# 32nbIoTrpi.net
KiCad netlist of a schematic drawn in EAGLE
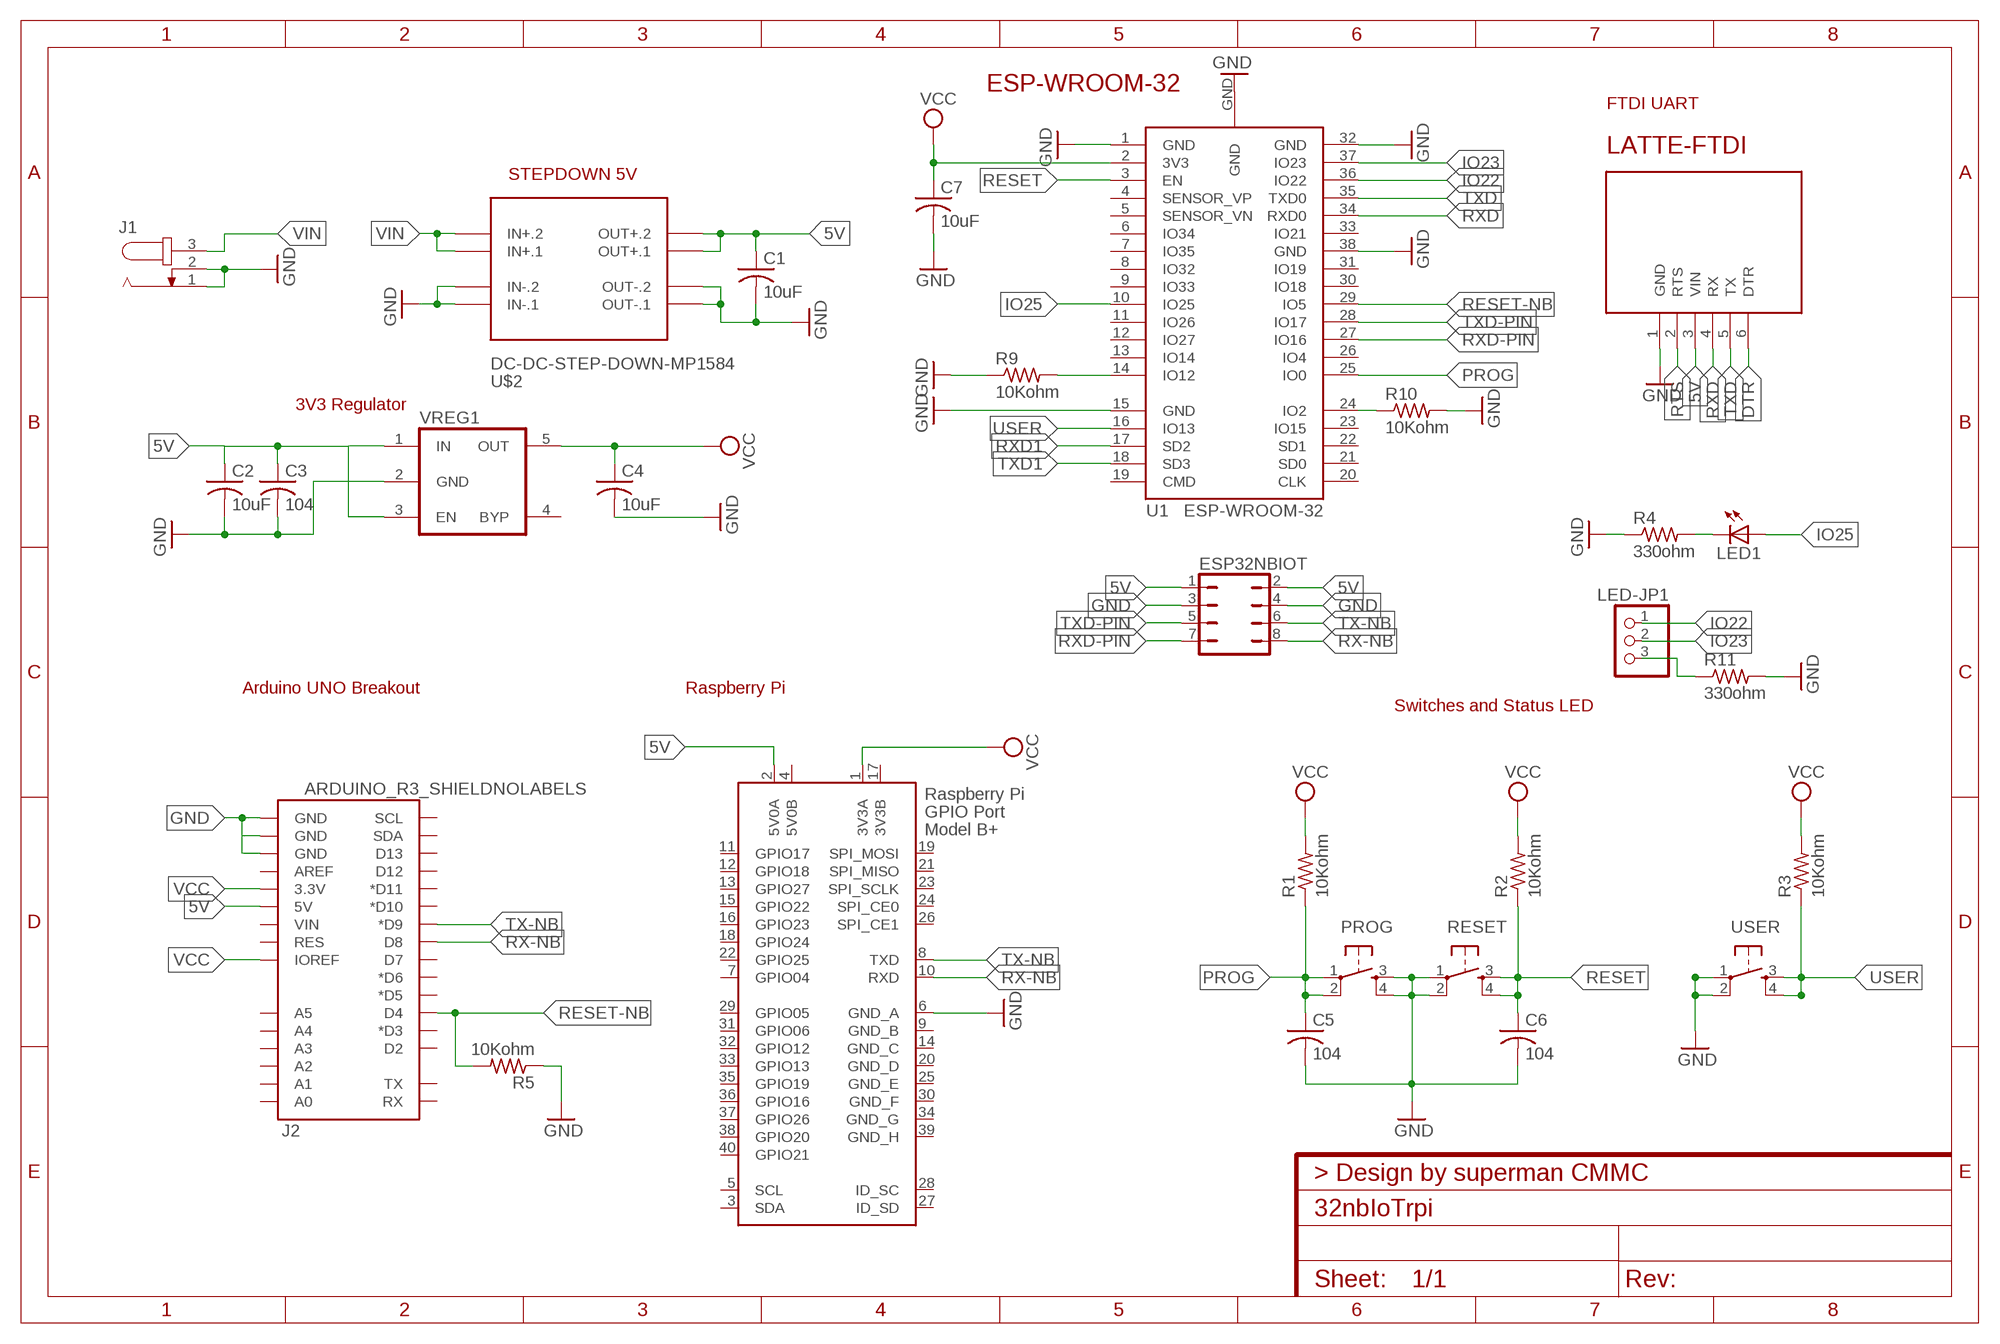
[diagram p0: schematic, sheet 1]

(export (version "E")
  (design (tool "Eeschema 10.0.6"))
  (components
    (comp (ref "C1")
      (value "10uF")
      (footprint "eagle-import:C0805")
      (libsource (lib "eagle-import") (part "C-USC0805"))
    )
    (comp (ref "C2")
      (value "10uF")
      (footprint "eagle-import:C0805")
      (libsource (lib "eagle-import") (part "C-USC0805"))
    )
    (comp (ref "C3")
      (value "104")
      (footprint "eagle-import:C0805")
      (libsource (lib "eagle-import") (part "C-USC0805"))
    )
    (comp (ref "C4")
      (value "10uF")
      (footprint "eagle-import:C0805")
      (libsource (lib "eagle-import") (part "C-USC0805"))
    )
    (comp (ref "C5")
      (value "104")
      (footprint "eagle-import:C0805")
      (libsource (lib "eagle-import") (part "C-USC0805"))
    )
    (comp (ref "C6")
      (value "104")
      (footprint "eagle-import:C0805")
      (libsource (lib "eagle-import") (part "C-USC0805"))
    )
    (comp (ref "C7")
      (value "10uF")
      (footprint "eagle-import:C0805")
      (libsource (lib "eagle-import") (part "C-USC0805"))
    )
    (comp (ref "ESP32NBIOT")
      (value "JP4Q")
      (footprint "eagle-import:JP4Q")
      (libsource (lib "eagle-import") (part "JP4Q"))
    )
    (comp (ref "J1")
      (value "JACK-PLUG1")
      (footprint "eagle-import:SPC4078")
      (libsource (lib "eagle-import") (part "JACK-PLUG1"))
    )
    (comp (ref "J2")
      (value "ARDUINO_R3_SHIELDNOLABELS")
      (footprint "eagle-import:UNO_R3_SHIELD_NOLABELS")
      (libsource (lib "eagle-import") (part "ARDUINO_R3_SHIELDNOLABELS"))
    )
    (comp (ref "LATTE-FTDI")
      (value "FTDI")
      (footprint "eagle-import:CMMC-FTDI")
      (libsource (lib "eagle-import") (part "FTDI"))
    )
    (comp (ref "LED-JP1")
      (value "PINHD-1X3/90")
      (footprint "eagle-import:1X03_90")
      (libsource (lib "eagle-import") (part "PINHD-1X3/90"))
    )
    (comp (ref "LED1")
      (value "LEDCHIPLED_0805")
      (footprint "eagle-import:CHIPLED_0805")
      (libsource (lib "eagle-import") (part "LEDCHIPLED_0805"))
    )
    (comp (ref "PROG")
      (value "TAC_SWITCHPTH")
      (footprint "eagle-import:TACTILE-PTH")
      (libsource (lib "eagle-import") (part "TAC_SWITCHPTH"))
    )
    (comp (ref "R1")
      (value "10Kohm")
      (footprint "eagle-import:R0805W")
      (libsource (lib "eagle-import") (part "R-US_R0805W"))
    )
    (comp (ref "R2")
      (value "10Kohm")
      (footprint "eagle-import:R0805W")
      (libsource (lib "eagle-import") (part "R-US_R0805W"))
    )
    (comp (ref "R3")
      (value "10Kohm")
      (footprint "eagle-import:R0805W")
      (libsource (lib "eagle-import") (part "R-US_R0805W"))
    )
    (comp (ref "R4")
      (value "330ohm")
      (footprint "eagle-import:R0805W")
      (libsource (lib "eagle-import") (part "R-US_R0805W"))
    )
    (comp (ref "R5")
      (value "10Kohm")
      (footprint "eagle-import:R0805W")
      (libsource (lib "eagle-import") (part "R-US_R0805W"))
    )
    (comp (ref "R9")
      (value "10Kohm")
      (footprint "eagle-import:R0805W")
      (libsource (lib "eagle-import") (part "R-US_R0805W"))
    )
    (comp (ref "R10")
      (value "10Kohm")
      (footprint "eagle-import:R0805W")
      (libsource (lib "eagle-import") (part "R-US_R0805W"))
    )
    (comp (ref "R11")
      (value "330ohm")
      (footprint "eagle-import:R0805W")
      (libsource (lib "eagle-import") (part "R-US_R0805W"))
    )
    (comp (ref "RESET")
      (value "TAC_SWITCHPTH")
      (footprint "eagle-import:TACTILE-PTH")
      (libsource (lib "eagle-import") (part "TAC_SWITCHPTH"))
    )
    (comp (ref "U$2")
      (value "DC-DC-STEP-DOWN-MP1584")
      (footprint "eagle-import:DC-DC-STEP-DOWN-MP1584")
      (libsource (lib "eagle-import") (part "DC-DC-STEP-DOWN-MP1584"))
    )
    (comp (ref "U1")
      (value "ESP-WROOM-32")
      (footprint "eagle-import:ESP-WROOM-32")
      (libsource (lib "eagle-import") (part "ESP-WROOM-32"))
    )
    (comp (ref "USER")
      (value "TAC_SWITCHPTH")
      (footprint "eagle-import:TACTILE-PTH")
      (libsource (lib "eagle-import") (part "TAC_SWITCHPTH"))
    )
    (comp (ref "VREG1")
      (value "VREG_5PINS-SOT-23-5")
      (footprint "eagle-import:SOT-23-5")
      (libsource (lib "eagle-import") (part "VREG_5PINS-SOT-23-5"))
    )
    (comp (ref "X2")
      (value "RASPI_BOARD_B+#_E0")
      (footprint "eagle-import:RASPI_BOARD_B+_EDGES_0DRILL")
      (libsource (lib "eagle-import") (part "RASPI_BOARD_B+#_E0"))
    )
  )
  (nets
    (net (code "1") (name "/3V3B") (class "Default")
      (node (ref "X2") (pin "17") (pinfunction "3V3B_17") (pintype "power_in"))
    )
    (net (code "2") (name "/5V0B") (class "Default")
      (node (ref "X2") (pin "4") (pinfunction "5V0B_4") (pintype "power_in"))
    )
    (net (code "3") (name "/GND_B") (class "Default")
      (node (ref "X2") (pin "9") (pinfunction "GND_B_9") (pintype "power_in"))
    )
    (net (code "4") (name "/GND_C") (class "Default")
      (node (ref "X2") (pin "14") (pinfunction "GND_C_14") (pintype "power_in"))
    )
    (net (code "5") (name "/GND_D") (class "Default")
      (node (ref "X2") (pin "20") (pinfunction "GND_D_20") (pintype "power_in"))
    )
    (net (code "6") (name "/GND_E") (class "Default")
      (node (ref "X2") (pin "25") (pinfunction "GND_E_25") (pintype "power_in"))
    )
    (net (code "7") (name "/GND_F") (class "Default")
      (node (ref "X2") (pin "30") (pinfunction "GND_F_30") (pintype "power_in"))
    )
    (net (code "8") (name "/GND_G") (class "Default")
      (node (ref "X2") (pin "34") (pinfunction "GND_G_34") (pintype "power_in"))
    )
    (net (code "9") (name "/GND_H") (class "Default")
      (node (ref "X2") (pin "39") (pinfunction "GND_H_39") (pintype "power_in"))
    )
    (net (code "10") (name "5V") (class "Default")
      (node (ref "C1") (pin "1") (pinfunction "1_1") (pintype "passive"))
      (node (ref "C2") (pin "1") (pinfunction "1_1") (pintype "passive"))
      (node (ref "C3") (pin "1") (pinfunction "1_1") (pintype "passive"))
      (node (ref "ESP32NBIOT") (pin "1") (pinfunction "1_1") (pintype "passive"))
      (node (ref "ESP32NBIOT") (pin "2") (pinfunction "2_2") (pintype "passive"))
      (node (ref "J2") (pin "5V") (pinfunction "5V_5V") (pintype "bidirectional"))
      (node (ref "LATTE-FTDI") (pin "3") (pinfunction "VIN_3") (pintype "bidirectional"))
      (node (ref "U$2") (pin "OUT+.1") (pinfunction "OUT+.1_OUT+.1") (pintype "bidirectional"))
      (node (ref "U$2") (pin "OUT+.2") (pinfunction "OUT+.2_OUT+.2") (pintype "bidirectional"))
      (node (ref "VREG1") (pin "1") (pinfunction "IN_1") (pintype "bidirectional"))
      (node (ref "VREG1") (pin "3") (pinfunction "EN_3") (pintype "bidirectional"))
      (node (ref "X2") (pin "2") (pinfunction "5V0A_2") (pintype "power_in"))
    )
    (net (code "11") (name "DTR") (class "Default")
      (node (ref "LATTE-FTDI") (pin "6") (pinfunction "DTR_6") (pintype "bidirectional"))
    )
    (net (code "12") (name "GND") (class "Default")
      (node (ref "C1") (pin "2") (pinfunction "2_2") (pintype "passive"))
      (node (ref "C2") (pin "2") (pinfunction "2_2") (pintype "passive"))
      (node (ref "C3") (pin "2") (pinfunction "2_2") (pintype "passive"))
      (node (ref "C4") (pin "2") (pinfunction "2_2") (pintype "passive"))
      (node (ref "C5") (pin "2") (pinfunction "2_2") (pintype "passive"))
      (node (ref "C6") (pin "2") (pinfunction "2_2") (pintype "passive"))
      (node (ref "C7") (pin "2") (pinfunction "2_2") (pintype "passive"))
      (node (ref "ESP32NBIOT") (pin "3") (pinfunction "3_3") (pintype "passive"))
      (node (ref "ESP32NBIOT") (pin "4") (pinfunction "4_4") (pintype "passive"))
      (node (ref "J1") (pin "1") (pinfunction "1_1") (pintype "passive"))
      (node (ref "J1") (pin "2") (pinfunction "2_2") (pintype "passive"))
      (node (ref "J2") (pin "GND@0") (pinfunction "GND_GND@0") (pintype "bidirectional"))
      (node (ref "J2") (pin "GND@1") (pinfunction "GND_GND@1") (pintype "bidirectional"))
      (node (ref "J2") (pin "GND@2") (pinfunction "GND_GND@2") (pintype "bidirectional"))
      (node (ref "LATTE-FTDI") (pin "1") (pinfunction "GND_1") (pintype "bidirectional"))
      (node (ref "PROG") (pin "3") (pinfunction "3_3") (pintype "passive"))
      (node (ref "PROG") (pin "4") (pinfunction "4_4") (pintype "passive"))
      (node (ref "R10") (pin "2") (pinfunction "2_2") (pintype "passive"))
      (node (ref "R11") (pin "2") (pinfunction "2_2") (pintype "passive"))
      (node (ref "R4") (pin "1") (pinfunction "1_1") (pintype "passive"))
      (node (ref "R5") (pin "1") (pinfunction "1_1") (pintype "passive"))
      (node (ref "R9") (pin "1") (pinfunction "1_1") (pintype "passive"))
      (node (ref "RESET") (pin "1") (pinfunction "1_1") (pintype "passive"))
      (node (ref "RESET") (pin "2") (pinfunction "2_2") (pintype "passive"))
      (node (ref "U$2") (pin "IN-.1") (pinfunction "IN-.1_IN-.1") (pintype "bidirectional"))
      (node (ref "U$2") (pin "IN-.2") (pinfunction "IN-.2_IN-.2") (pintype "bidirectional"))
      (node (ref "U$2") (pin "OUT-.1") (pinfunction "OUT-.1_OUT-.1") (pintype "bidirectional"))
      (node (ref "U$2") (pin "OUT-.2") (pinfunction "OUT-.2_OUT-.2") (pintype "bidirectional"))
      (node (ref "U1") (pin "1") (pinfunction "GND_1") (pintype "power_in"))
      (node (ref "U1") (pin "15") (pinfunction "GND_15") (pintype "power_in"))
      (node (ref "U1") (pin "32") (pinfunction "GND_32") (pintype "power_in"))
      (node (ref "U1") (pin "38") (pinfunction "GND_38") (pintype "power_in"))
      (node (ref "U1") (pin "GND") (pinfunction "GND_GND") (pintype "bidirectional"))
      (node (ref "USER") (pin "1") (pinfunction "1_1") (pintype "passive"))
      (node (ref "USER") (pin "2") (pinfunction "2_2") (pintype "passive"))
      (node (ref "VREG1") (pin "2") (pinfunction "GND_2") (pintype "bidirectional"))
      (node (ref "X2") (pin "6") (pinfunction "GND_A_6") (pintype "power_in"))
    )
    (net (code "13") (name "IO22") (class "Default")
      (node (ref "LED-JP1") (pin "1") (pinfunction "1_1") (pintype "passive"))
      (node (ref "U1") (pin "36") (pinfunction "IO22_36") (pintype "bidirectional"))
    )
    (net (code "14") (name "IO23") (class "Default")
      (node (ref "LED-JP1") (pin "2") (pinfunction "2_2") (pintype "passive"))
      (node (ref "U1") (pin "37") (pinfunction "IO23_37") (pintype "bidirectional"))
    )
    (net (code "15") (name "IO25") (class "Default")
      (node (ref "LED1") (pin "A") (pinfunction "A_A") (pintype "passive"))
      (node (ref "U1") (pin "10") (pinfunction "IO25_10") (pintype "bidirectional"))
    )
    (net (code "16") (name "Net-(LED-JP1-Pad3)") (class "Default")
      (node (ref "LED-JP1") (pin "3") (pinfunction "3_3") (pintype "passive"))
      (node (ref "R11") (pin "1") (pinfunction "1_1") (pintype "passive"))
    )
    (net (code "17") (name "Net-(LED1-PadC)") (class "Default")
      (node (ref "LED1") (pin "C") (pinfunction "C_C") (pintype "passive"))
      (node (ref "R4") (pin "2") (pinfunction "2_2") (pintype "passive"))
    )
    (net (code "18") (name "Net-(U1-IO2)") (class "Default")
      (node (ref "R10") (pin "1") (pinfunction "1_1") (pintype "passive"))
      (node (ref "U1") (pin "24") (pinfunction "IO2_24") (pintype "bidirectional"))
    )
    (net (code "19") (name "Net-(U1-IO12)") (class "Default")
      (node (ref "R9") (pin "2") (pinfunction "2_2") (pintype "passive"))
      (node (ref "U1") (pin "14") (pinfunction "IO12_14") (pintype "bidirectional"))
    )
    (net (code "20") (name "PROG") (class "Default")
      (node (ref "C5") (pin "1") (pinfunction "1_1") (pintype "passive"))
      (node (ref "PROG") (pin "1") (pinfunction "1_1") (pintype "passive"))
      (node (ref "PROG") (pin "2") (pinfunction "2_2") (pintype "passive"))
      (node (ref "R1") (pin "1") (pinfunction "1_1") (pintype "passive"))
      (node (ref "U1") (pin "25") (pinfunction "IO0_25") (pintype "bidirectional"))
    )
    (net (code "21") (name "RESET") (class "Default")
      (node (ref "C6") (pin "1") (pinfunction "1_1") (pintype "passive"))
      (node (ref "R2") (pin "1") (pinfunction "1_1") (pintype "passive"))
      (node (ref "RESET") (pin "3") (pinfunction "3_3") (pintype "passive"))
      (node (ref "RESET") (pin "4") (pinfunction "4_4") (pintype "passive"))
      (node (ref "U1") (pin "3") (pinfunction "EN_3") (pintype "input"))
    )
    (net (code "22") (name "RESET-NB") (class "Default")
      (node (ref "J2") (pin "D4") (pinfunction "D4_D4") (pintype "bidirectional"))
      (node (ref "R5") (pin "2") (pinfunction "2_2") (pintype "passive"))
      (node (ref "U1") (pin "29") (pinfunction "IO5_29") (pintype "bidirectional"))
    )
    (net (code "23") (name "RTS") (class "Default")
      (node (ref "LATTE-FTDI") (pin "2") (pinfunction "RTS_2") (pintype "bidirectional"))
    )
    (net (code "24") (name "RX-NB") (class "Default")
      (node (ref "ESP32NBIOT") (pin "8") (pinfunction "8_8") (pintype "passive"))
      (node (ref "J2") (pin "D8") (pinfunction "D8_D8") (pintype "bidirectional"))
      (node (ref "X2") (pin "10") (pinfunction "RXD_10") (pintype "bidirectional"))
    )
    (net (code "25") (name "RXD") (class "Default")
      (node (ref "LATTE-FTDI") (pin "4") (pinfunction "RX_4") (pintype "bidirectional"))
      (node (ref "U1") (pin "34") (pinfunction "RXD0_34") (pintype "bidirectional"))
    )
    (net (code "26") (name "RXD-PIN") (class "Default")
      (node (ref "ESP32NBIOT") (pin "7") (pinfunction "7_7") (pintype "passive"))
      (node (ref "U1") (pin "27") (pinfunction "IO16_27") (pintype "bidirectional"))
    )
    (net (code "27") (name "RXD1") (class "Default")
      (node (ref "U1") (pin "17") (pinfunction "SD2_17") (pintype "bidirectional"))
    )
    (net (code "28") (name "TX-NB") (class "Default")
      (node (ref "ESP32NBIOT") (pin "6") (pinfunction "6_6") (pintype "passive"))
      (node (ref "J2") (pin "D9") (pinfunction "*D9_D9") (pintype "bidirectional"))
      (node (ref "X2") (pin "8") (pinfunction "TXD_8") (pintype "bidirectional"))
    )
    (net (code "29") (name "TXD") (class "Default")
      (node (ref "LATTE-FTDI") (pin "5") (pinfunction "TX_5") (pintype "bidirectional"))
      (node (ref "U1") (pin "35") (pinfunction "TXD0_35") (pintype "bidirectional"))
    )
    (net (code "30") (name "TXD-PIN") (class "Default")
      (node (ref "ESP32NBIOT") (pin "5") (pinfunction "5_5") (pintype "passive"))
      (node (ref "U1") (pin "28") (pinfunction "IO17_28") (pintype "bidirectional"))
    )
    (net (code "31") (name "TXD1") (class "Default")
      (node (ref "U1") (pin "18") (pinfunction "SD3_18") (pintype "bidirectional"))
    )
    (net (code "32") (name "USER") (class "Default")
      (node (ref "R3") (pin "1") (pinfunction "1_1") (pintype "passive"))
      (node (ref "U1") (pin "16") (pinfunction "IO13_16") (pintype "bidirectional"))
      (node (ref "USER") (pin "3") (pinfunction "3_3") (pintype "passive"))
      (node (ref "USER") (pin "4") (pinfunction "4_4") (pintype "passive"))
    )
    (net (code "33") (name "VCC") (class "Default")
      (node (ref "C4") (pin "1") (pinfunction "1_1") (pintype "passive"))
      (node (ref "C7") (pin "1") (pinfunction "1_1") (pintype "passive"))
      (node (ref "J2") (pin "3.3V") (pinfunction "3.3V_3.3V") (pintype "bidirectional"))
      (node (ref "J2") (pin "IOREF") (pinfunction "IOREF_IOREF") (pintype "bidirectional"))
      (node (ref "R1") (pin "2") (pinfunction "2_2") (pintype "passive"))
      (node (ref "R2") (pin "2") (pinfunction "2_2") (pintype "passive"))
      (node (ref "R3") (pin "2") (pinfunction "2_2") (pintype "passive"))
      (node (ref "U1") (pin "2") (pinfunction "3V3_2") (pintype "power_in"))
      (node (ref "VREG1") (pin "5") (pinfunction "OUT_5") (pintype "bidirectional"))
      (node (ref "X2") (pin "1") (pinfunction "3V3A_1") (pintype "power_in"))
    )
    (net (code "34") (name "VIN") (class "Default")
      (node (ref "J1") (pin "3") (pinfunction "3_3") (pintype "passive"))
      (node (ref "U$2") (pin "IN+.1") (pinfunction "IN+.1_IN+.1") (pintype "bidirectional"))
      (node (ref "U$2") (pin "IN+.2") (pinfunction "IN+.2_IN+.2") (pintype "bidirectional"))
    )
    (net (code "35") (name "unconnected-(J2-*D3-PadD3)") (class "Default")
      (node (ref "J2") (pin "D3") (pinfunction "*D3_D3") (pintype "bidirectional"))
    )
    (net (code "36") (name "unconnected-(J2-*D5-PadD5)") (class "Default")
      (node (ref "J2") (pin "D5") (pinfunction "*D5_D5") (pintype "bidirectional"))
    )
    (net (code "37") (name "unconnected-(J2-*D6-PadD6)") (class "Default")
      (node (ref "J2") (pin "D6") (pinfunction "*D6_D6") (pintype "bidirectional"))
    )
    (net (code "38") (name "unconnected-(J2-*D10-PadD10)") (class "Default")
      (node (ref "J2") (pin "D10") (pinfunction "*D10_D10") (pintype "bidirectional"))
    )
    (net (code "39") (name "unconnected-(J2-*D11-PadD11)") (class "Default")
      (node (ref "J2") (pin "D11") (pinfunction "*D11_D11") (pintype "bidirectional"))
    )
    (net (code "40") (name "unconnected-(J2-PadA0)") (class "Default")
      (node (ref "J2") (pin "A0") (pinfunction "A0_A0") (pintype "bidirectional"))
    )
    (net (code "41") (name "unconnected-(J2-PadA1)") (class "Default")
      (node (ref "J2") (pin "A1") (pinfunction "A1_A1") (pintype "bidirectional"))
    )
    (net (code "42") (name "unconnected-(J2-PadA2)") (class "Default")
      (node (ref "J2") (pin "A2") (pinfunction "A2_A2") (pintype "bidirectional"))
    )
    (net (code "43") (name "unconnected-(J2-PadA3)") (class "Default")
      (node (ref "J2") (pin "A3") (pinfunction "A3_A3") (pintype "bidirectional"))
    )
    (net (code "44") (name "unconnected-(J2-PadA4)") (class "Default")
      (node (ref "J2") (pin "A4") (pinfunction "A4_A4") (pintype "bidirectional"))
    )
    (net (code "45") (name "unconnected-(J2-PadA5)") (class "Default")
      (node (ref "J2") (pin "A5") (pinfunction "A5_A5") (pintype "bidirectional"))
    )
    (net (code "46") (name "unconnected-(J2-PadAREF)") (class "Default")
      (node (ref "J2") (pin "AREF") (pinfunction "AREF_AREF") (pintype "bidirectional"))
    )
    (net (code "47") (name "unconnected-(J2-PadD2)") (class "Default")
      (node (ref "J2") (pin "D2") (pinfunction "D2_D2") (pintype "bidirectional"))
    )
    (net (code "48") (name "unconnected-(J2-PadD7)") (class "Default")
      (node (ref "J2") (pin "D7") (pinfunction "D7_D7") (pintype "bidirectional"))
    )
    (net (code "49") (name "unconnected-(J2-PadD12)") (class "Default")
      (node (ref "J2") (pin "D12") (pinfunction "D12_D12") (pintype "bidirectional"))
    )
    (net (code "50") (name "unconnected-(J2-PadD13)") (class "Default")
      (node (ref "J2") (pin "D13") (pinfunction "D13_D13") (pintype "bidirectional"))
    )
    (net (code "51") (name "unconnected-(J2-PadRES)") (class "Default")
      (node (ref "J2") (pin "RES") (pinfunction "RES_RES") (pintype "bidirectional"))
    )
    (net (code "52") (name "unconnected-(J2-PadRX)") (class "Default")
      (node (ref "J2") (pin "RX") (pinfunction "RX_RX") (pintype "bidirectional"))
    )
    (net (code "53") (name "unconnected-(J2-PadSCL)") (class "Default")
      (node (ref "J2") (pin "SCL") (pinfunction "SCL_SCL") (pintype "bidirectional"))
    )
    (net (code "54") (name "unconnected-(J2-PadSDA)") (class "Default")
      (node (ref "J2") (pin "SDA") (pinfunction "SDA_SDA") (pintype "bidirectional"))
    )
    (net (code "55") (name "unconnected-(J2-PadTX)") (class "Default")
      (node (ref "J2") (pin "TX") (pinfunction "TX_TX") (pintype "bidirectional"))
    )
    (net (code "56") (name "unconnected-(J2-PadVIN)") (class "Default")
      (node (ref "J2") (pin "VIN") (pinfunction "VIN_VIN") (pintype "bidirectional"))
    )
    (net (code "57") (name "unconnected-(U1-CLK-Pad20)") (class "Default")
      (node (ref "U1") (pin "20") (pinfunction "CLK_20") (pintype "bidirectional"))
    )
    (net (code "58") (name "unconnected-(U1-CMD-Pad19)") (class "Default")
      (node (ref "U1") (pin "19") (pinfunction "CMD_19") (pintype "bidirectional"))
    )
    (net (code "59") (name "unconnected-(U1-IO4-Pad26)") (class "Default")
      (node (ref "U1") (pin "26") (pinfunction "IO4_26") (pintype "bidirectional"))
    )
    (net (code "60") (name "unconnected-(U1-IO14-Pad13)") (class "Default")
      (node (ref "U1") (pin "13") (pinfunction "IO14_13") (pintype "bidirectional"))
    )
    (net (code "61") (name "unconnected-(U1-IO15-Pad23)") (class "Default")
      (node (ref "U1") (pin "23") (pinfunction "IO15_23") (pintype "bidirectional"))
    )
    (net (code "62") (name "unconnected-(U1-IO18-Pad30)") (class "Default")
      (node (ref "U1") (pin "30") (pinfunction "IO18_30") (pintype "bidirectional"))
    )
    (net (code "63") (name "unconnected-(U1-IO19-Pad31)") (class "Default")
      (node (ref "U1") (pin "31") (pinfunction "IO19_31") (pintype "bidirectional"))
    )
    (net (code "64") (name "unconnected-(U1-IO21-Pad33)") (class "Default")
      (node (ref "U1") (pin "33") (pinfunction "IO21_33") (pintype "bidirectional"))
    )
    (net (code "65") (name "unconnected-(U1-IO26-Pad11)") (class "Default")
      (node (ref "U1") (pin "11") (pinfunction "IO26_11") (pintype "bidirectional"))
    )
    (net (code "66") (name "unconnected-(U1-IO27-Pad12)") (class "Default")
      (node (ref "U1") (pin "12") (pinfunction "IO27_12") (pintype "bidirectional"))
    )
    (net (code "67") (name "unconnected-(U1-IO32-Pad8)") (class "Default")
      (node (ref "U1") (pin "8") (pinfunction "IO32_8") (pintype "bidirectional"))
    )
    (net (code "68") (name "unconnected-(U1-IO33-Pad9)") (class "Default")
      (node (ref "U1") (pin "9") (pinfunction "IO33_9") (pintype "bidirectional"))
    )
    (net (code "69") (name "unconnected-(U1-IO34-Pad6)") (class "Default")
      (node (ref "U1") (pin "6") (pinfunction "IO34_6") (pintype "bidirectional"))
    )
    (net (code "70") (name "unconnected-(U1-IO35-Pad7)") (class "Default")
      (node (ref "U1") (pin "7") (pinfunction "IO35_7") (pintype "bidirectional"))
    )
    (net (code "71") (name "unconnected-(U1-SD0-Pad21)") (class "Default")
      (node (ref "U1") (pin "21") (pinfunction "SD0_21") (pintype "bidirectional"))
    )
    (net (code "72") (name "unconnected-(U1-SD1-Pad22)") (class "Default")
      (node (ref "U1") (pin "22") (pinfunction "SD1_22") (pintype "bidirectional"))
    )
    (net (code "73") (name "unconnected-(U1-SENSOR_VN-Pad5)") (class "Default")
      (node (ref "U1") (pin "5") (pinfunction "SENSOR_VN_5") (pintype "bidirectional"))
    )
    (net (code "74") (name "unconnected-(U1-SENSOR_VP-Pad4)") (class "Default")
      (node (ref "U1") (pin "4") (pinfunction "SENSOR_VP_4") (pintype "bidirectional"))
    )
    (net (code "75") (name "unconnected-(VREG1-BYP-Pad4)") (class "Default")
      (node (ref "VREG1") (pin "4") (pinfunction "BYP_4") (pintype "bidirectional"))
    )
    (net (code "76") (name "unconnected-(X2-GPIO04-Pad7)") (class "Default")
      (node (ref "X2") (pin "7") (pinfunction "GPIO04_7") (pintype "bidirectional"))
    )
    (net (code "77") (name "unconnected-(X2-GPIO05-Pad29)") (class "Default")
      (node (ref "X2") (pin "29") (pinfunction "GPIO05_29") (pintype "no_connect"))
    )
    (net (code "78") (name "unconnected-(X2-GPIO06-Pad31)") (class "Default")
      (node (ref "X2") (pin "31") (pinfunction "GPIO06_31") (pintype "no_connect"))
    )
    (net (code "79") (name "unconnected-(X2-GPIO12-Pad32)") (class "Default")
      (node (ref "X2") (pin "32") (pinfunction "GPIO12_32") (pintype "no_connect"))
    )
    (net (code "80") (name "unconnected-(X2-GPIO13-Pad33)") (class "Default")
      (node (ref "X2") (pin "33") (pinfunction "GPIO13_33") (pintype "no_connect"))
    )
    (net (code "81") (name "unconnected-(X2-GPIO16-Pad36)") (class "Default")
      (node (ref "X2") (pin "36") (pinfunction "GPIO16_36") (pintype "no_connect"))
    )
    (net (code "82") (name "unconnected-(X2-GPIO17-Pad11)") (class "Default")
      (node (ref "X2") (pin "11") (pinfunction "GPIO17_11") (pintype "bidirectional"))
    )
    (net (code "83") (name "unconnected-(X2-GPIO18-Pad12)") (class "Default")
      (node (ref "X2") (pin "12") (pinfunction "GPIO18_12") (pintype "bidirectional"))
    )
    (net (code "84") (name "unconnected-(X2-GPIO19-Pad35)") (class "Default")
      (node (ref "X2") (pin "35") (pinfunction "GPIO19_35") (pintype "no_connect"))
    )
    (net (code "85") (name "unconnected-(X2-GPIO20-Pad38)") (class "Default")
      (node (ref "X2") (pin "38") (pinfunction "GPIO20_38") (pintype "no_connect"))
    )
    (net (code "86") (name "unconnected-(X2-GPIO21-Pad40)") (class "Default")
      (node (ref "X2") (pin "40") (pinfunction "GPIO21_40") (pintype "no_connect"))
    )
    (net (code "87") (name "unconnected-(X2-GPIO22-Pad15)") (class "Default")
      (node (ref "X2") (pin "15") (pinfunction "GPIO22_15") (pintype "bidirectional"))
    )
    (net (code "88") (name "unconnected-(X2-GPIO23-Pad16)") (class "Default")
      (node (ref "X2") (pin "16") (pinfunction "GPIO23_16") (pintype "bidirectional"))
    )
    (net (code "89") (name "unconnected-(X2-GPIO24-Pad18)") (class "Default")
      (node (ref "X2") (pin "18") (pinfunction "GPIO24_18") (pintype "bidirectional"))
    )
    (net (code "90") (name "unconnected-(X2-GPIO25-Pad22)") (class "Default")
      (node (ref "X2") (pin "22") (pinfunction "GPIO25_22") (pintype "bidirectional"))
    )
    (net (code "91") (name "unconnected-(X2-GPIO26-Pad37)") (class "Default")
      (node (ref "X2") (pin "37") (pinfunction "GPIO26_37") (pintype "no_connect"))
    )
    (net (code "92") (name "unconnected-(X2-GPIO27-Pad13)") (class "Default")
      (node (ref "X2") (pin "13") (pinfunction "GPIO27_13") (pintype "bidirectional"))
    )
    (net (code "93") (name "unconnected-(X2-ID_SC-Pad28)") (class "Default")
      (node (ref "X2") (pin "28") (pinfunction "ID_SC_28") (pintype "no_connect"))
    )
    (net (code "94") (name "unconnected-(X2-ID_SD-Pad27)") (class "Default")
      (node (ref "X2") (pin "27") (pinfunction "ID_SD_27") (pintype "no_connect"))
    )
    (net (code "95") (name "unconnected-(X2-SCL-Pad5)") (class "Default")
      (node (ref "X2") (pin "5") (pinfunction "SCL_5") (pintype "bidirectional"))
    )
    (net (code "96") (name "unconnected-(X2-SDA-Pad3)") (class "Default")
      (node (ref "X2") (pin "3") (pinfunction "SDA_3") (pintype "bidirectional"))
    )
    (net (code "97") (name "unconnected-(X2-SPI_CE0-Pad24)") (class "Default")
      (node (ref "X2") (pin "24") (pinfunction "SPI_CE0_24") (pintype "bidirectional"))
    )
    (net (code "98") (name "unconnected-(X2-SPI_CE1-Pad26)") (class "Default")
      (node (ref "X2") (pin "26") (pinfunction "SPI_CE1_26") (pintype "bidirectional"))
    )
    (net (code "99") (name "unconnected-(X2-SPI_MISO-Pad21)") (class "Default")
      (node (ref "X2") (pin "21") (pinfunction "SPI_MISO_21") (pintype "bidirectional"))
    )
    (net (code "100") (name "unconnected-(X2-SPI_MOSI-Pad19)") (class "Default")
      (node (ref "X2") (pin "19") (pinfunction "SPI_MOSI_19") (pintype "bidirectional"))
    )
    (net (code "101") (name "unconnected-(X2-SPI_SCLK-Pad23)") (class "Default")
      (node (ref "X2") (pin "23") (pinfunction "SPI_SCLK_23") (pintype "bidirectional"))
    )
  )
)
